# Mach_trai_tim.net
KiCad netlist of a schematic drawn in Altium Designer
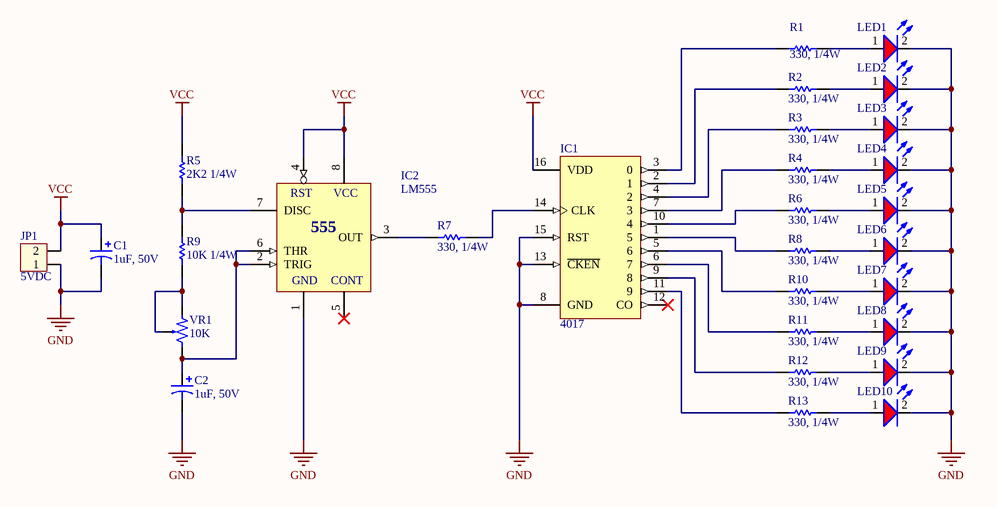
[diagram p0: Mach trai tim.SchDoc]

(export (version "E")
  (design (tool "Eeschema 10.0.6"))
  (components
    (comp (ref "C1")
      (value "1uF, 50V")
      (footprint "CAP_1UF_50V")
      (description "CAP GSR 0511 10uF 16V 20%")
      (fields (field (name "Comment") "GSR10M016-0511TAF"))
      (libsource (lib "lpson") (part "GSR10M016-0511TAF"))
    )
    (comp (ref "C2")
      (value "1uF, 50V")
      (footprint "CAP_1UF_50V")
      (description "CAP GSR 0511 10uF 16V 20%")
      (fields (field (name "Comment") "GSR10M016-0511TAF"))
      (libsource (lib "lpson") (part "GSR10M016-0511TAF"))
    )
    (comp (ref "IC1")
      (value "4017")
      (footprint "74HC4017")
      (description "Decade Counter/Divider with 10 Decoded Outputs")
      (fields (field (name "DESIGNED BY") "VanDungEvn"))
      (libsource (lib "lpson") (part "4017"))
    )
    (comp (ref "IC2")
      (value "LM555")
      (footprint "LM555")
      (description "Timer")
      (libsource (lib "lpson") (part "LM555"))
    )
    (comp (ref "JP1")
      (value "5VDC")
      (footprint "CON2")
      (description "Connector 2")
      (libsource (lib "lpson") (part "Con2"))
    )
    (comp (ref "LED1")
      (value "LED_R_5")
      (footprint "LED5R")
      (description "LED Red 5mm")
      (libsource (lib "lpson") (part "LED_RED_5MM"))
    )
    (comp (ref "LED2")
      (value "LED_R_5")
      (footprint "LED5R")
      (description "LED Red 5mm")
      (libsource (lib "lpson") (part "LED_RED_5MM"))
    )
    (comp (ref "LED3")
      (value "LED_R_5")
      (footprint "LED5R")
      (description "LED Red 5mm")
      (libsource (lib "lpson") (part "LED_RED_5MM"))
    )
    (comp (ref "LED4")
      (value "LED_R_5")
      (footprint "LED5R")
      (description "LED Red 5mm")
      (libsource (lib "lpson") (part "LED_RED_5MM"))
    )
    (comp (ref "LED5")
      (value "LED_R_5")
      (footprint "LED5R")
      (description "LED Red 5mm")
      (libsource (lib "lpson") (part "LED_RED_5MM"))
    )
    (comp (ref "LED6")
      (value "LED_R_5")
      (footprint "LED5R")
      (description "LED Red 5mm")
      (libsource (lib "lpson") (part "LED_RED_5MM"))
    )
    (comp (ref "LED7")
      (value "LED_R_5")
      (footprint "LED5R")
      (description "LED Red 5mm")
      (libsource (lib "lpson") (part "LED_RED_5MM"))
    )
    (comp (ref "LED8")
      (value "LED_R_5")
      (footprint "LED5R")
      (description "LED Red 5mm")
      (libsource (lib "lpson") (part "LED_RED_5MM"))
    )
    (comp (ref "LED9")
      (value "LED_R_5")
      (footprint "LED5R")
      (description "LED Red 5mm")
      (libsource (lib "lpson") (part "LED_RED_5MM"))
    )
    (comp (ref "LED10")
      (value "LED_R_5")
      (footprint "LED5R")
      (description "LED Red 5mm")
      (libsource (lib "lpson") (part "LED_RED_5MM"))
    )
    (comp (ref "R1")
      (value "330, 1/4W")
      (footprint "RES 1/4W CFR25")
      (description "RES CF AXIAL-0.3 5% 1/4W 1K")
      (fields (field (name "Comment") "CF1/4W1KJ25"))
      (libsource (lib "lpson") (part "CF1/4W1KJ25"))
    )
    (comp (ref "R2")
      (value "330, 1/4W")
      (footprint "RES 1/4W CFR25")
      (description "RES CF AXIAL-0.3 5% 1/4W 1K")
      (fields (field (name "Comment") "CF1/4W1KJ25"))
      (libsource (lib "lpson") (part "CF1/4W1KJ25"))
    )
    (comp (ref "R3")
      (value "330, 1/4W")
      (footprint "RES 1/4W CFR25")
      (description "RES CF AXIAL-0.3 5% 1/4W 1K")
      (fields (field (name "Comment") "CF1/4W1KJ25"))
      (libsource (lib "lpson") (part "CF1/4W1KJ25"))
    )
    (comp (ref "R4")
      (value "330, 1/4W")
      (footprint "RES 1/4W CFR25")
      (description "RES CF AXIAL-0.3 5% 1/4W 1K")
      (fields (field (name "Comment") "CF1/4W1KJ25"))
      (libsource (lib "lpson") (part "CF1/4W1KJ25"))
    )
    (comp (ref "R5")
      (value "2K2 1/4W")
      (footprint "RES 1/4W CFR25")
      (description "RES CF AXIAL-0.3 5% 1/4W 1K")
      (fields (field (name "Comment") "CF1/4W1KJ25"))
      (libsource (lib "lpson") (part "CF1/4W1KJ25"))
    )
    (comp (ref "R6")
      (value "330, 1/4W")
      (footprint "RES 1/4W CFR25")
      (description "RES CF AXIAL-0.3 5% 1/4W 1K")
      (fields (field (name "Comment") "CF1/4W1KJ25"))
      (libsource (lib "lpson") (part "CF1/4W1KJ25"))
    )
    (comp (ref "R7")
      (value "330, 1/4W")
      (footprint "RES 1/4W CFR25")
      (description "RES CF AXIAL-0.3 5% 1/4W 1K")
      (fields (field (name "Comment") "CF1/4W1KJ25"))
      (libsource (lib "lpson") (part "CF1/4W1KJ25"))
    )
    (comp (ref "R8")
      (value "330, 1/4W")
      (footprint "RES 1/4W CFR25")
      (description "RES CF AXIAL-0.3 5% 1/4W 1K")
      (fields (field (name "Comment") "CF1/4W1KJ25"))
      (libsource (lib "lpson") (part "CF1/4W1KJ25"))
    )
    (comp (ref "R9")
      (value "10K 1/4W")
      (footprint "RES 1/4W CFR25")
      (description "RES CF AXIAL-0.3 5% 1/4W 1K")
      (fields (field (name "Comment") "CF1/4W1KJ25"))
      (libsource (lib "lpson") (part "CF1/4W1KJ25"))
    )
    (comp (ref "R10")
      (value "330, 1/4W")
      (footprint "RES 1/4W CFR25")
      (description "RES CF AXIAL-0.3 5% 1/4W 1K")
      (fields (field (name "Comment") "CF1/4W1KJ25"))
      (libsource (lib "lpson") (part "CF1/4W1KJ25"))
    )
    (comp (ref "R11")
      (value "330, 1/4W")
      (footprint "RES 1/4W CFR25")
      (description "RES CF AXIAL-0.3 5% 1/4W 1K")
      (fields (field (name "Comment") "CF1/4W1KJ25"))
      (libsource (lib "lpson") (part "CF1/4W1KJ25"))
    )
    (comp (ref "R12")
      (value "330, 1/4W")
      (footprint "RES 1/4W CFR25")
      (description "RES CF AXIAL-0.3 5% 1/4W 1K")
      (fields (field (name "Comment") "CF1/4W1KJ25"))
      (libsource (lib "lpson") (part "CF1/4W1KJ25"))
    )
    (comp (ref "R13")
      (value "330, 1/4W")
      (footprint "RES 1/4W CFR25")
      (description "RES CF AXIAL-0.3 5% 1/4W 1K")
      (fields (field (name "Comment") "CF1/4W1KJ25"))
      (libsource (lib "lpson") (part "CF1/4W1KJ25"))
    )
    (comp (ref "VR1")
      (value "10K")
      (footprint "VR1")
      (description "Var Resistor")
      (libsource (lib "lpson") (part "VR2"))
    )
  )
  (nets
    (net (code "1") (name "GND") (class "Default")
      (node (ref "C1") (pin "2") (pinfunction "2_2") (pintype "passive"))
      (node (ref "C2") (pin "2") (pinfunction "2_2") (pintype "passive"))
      (node (ref "IC1") (pin "13") (pinfunction "~{CKEN}_13") (pintype "input"))
      (node (ref "IC1") (pin "15") (pinfunction "RST_15") (pintype "input"))
      (node (ref "IC1") (pin "8") (pinfunction "GND_8") (pintype "power_in"))
      (node (ref "IC2") (pin "1") (pinfunction "GND_1") (pintype "power_in"))
      (node (ref "JP1") (pin "1") (pinfunction "1_1") (pintype "passive"))
      (node (ref "LED1") (pin "2") (pinfunction "K_2") (pintype "passive"))
      (node (ref "LED10") (pin "2") (pinfunction "K_2") (pintype "passive"))
      (node (ref "LED2") (pin "2") (pinfunction "K_2") (pintype "passive"))
      (node (ref "LED3") (pin "2") (pinfunction "K_2") (pintype "passive"))
      (node (ref "LED4") (pin "2") (pinfunction "K_2") (pintype "passive"))
      (node (ref "LED5") (pin "2") (pinfunction "K_2") (pintype "passive"))
      (node (ref "LED6") (pin "2") (pinfunction "K_2") (pintype "passive"))
      (node (ref "LED7") (pin "2") (pinfunction "K_2") (pintype "passive"))
      (node (ref "LED8") (pin "2") (pinfunction "K_2") (pintype "passive"))
      (node (ref "LED9") (pin "2") (pinfunction "K_2") (pintype "passive"))
    )
    (net (code "2") (name "Net-(IC1-0)") (class "Default")
      (node (ref "IC1") (pin "3") (pinfunction "0_3") (pintype "output"))
      (node (ref "R1") (pin "1") (pinfunction "1_1") (pintype "passive"))
    )
    (net (code "3") (name "Net-(IC1-1)") (class "Default")
      (node (ref "IC1") (pin "2") (pinfunction "1_2") (pintype "output"))
      (node (ref "R2") (pin "1") (pinfunction "1_1") (pintype "passive"))
    )
    (net (code "4") (name "Net-(IC1-2)") (class "Default")
      (node (ref "IC1") (pin "4") (pinfunction "2_4") (pintype "output"))
      (node (ref "R3") (pin "1") (pinfunction "1_1") (pintype "passive"))
    )
    (net (code "5") (name "Net-(IC1-3)") (class "Default")
      (node (ref "IC1") (pin "7") (pinfunction "3_7") (pintype "output"))
      (node (ref "R4") (pin "1") (pinfunction "1_1") (pintype "passive"))
    )
    (net (code "6") (name "Net-(IC1-4)") (class "Default")
      (node (ref "IC1") (pin "10") (pinfunction "4_10") (pintype "output"))
      (node (ref "R6") (pin "1") (pinfunction "1_1") (pintype "passive"))
    )
    (net (code "7") (name "Net-(IC1-5)") (class "Default")
      (node (ref "IC1") (pin "1") (pinfunction "5_1") (pintype "output"))
      (node (ref "R8") (pin "1") (pinfunction "1_1") (pintype "passive"))
    )
    (net (code "8") (name "Net-(IC1-6)") (class "Default")
      (node (ref "IC1") (pin "5") (pinfunction "6_5") (pintype "output"))
      (node (ref "R10") (pin "1") (pinfunction "1_1") (pintype "passive"))
    )
    (net (code "9") (name "Net-(IC1-7)") (class "Default")
      (node (ref "IC1") (pin "6") (pinfunction "7_6") (pintype "output"))
      (node (ref "R11") (pin "1") (pinfunction "1_1") (pintype "passive"))
    )
    (net (code "10") (name "Net-(IC1-8)") (class "Default")
      (node (ref "IC1") (pin "9") (pinfunction "8_9") (pintype "output"))
      (node (ref "R12") (pin "1") (pinfunction "1_1") (pintype "passive"))
    )
    (net (code "11") (name "Net-(IC1-9)") (class "Default")
      (node (ref "IC1") (pin "11") (pinfunction "9_11") (pintype "output"))
      (node (ref "R13") (pin "1") (pinfunction "1_1") (pintype "passive"))
    )
    (net (code "12") (name "Net-(IC1-CLK)") (class "Default")
      (node (ref "IC1") (pin "14") (pinfunction "CLK_14") (pintype "input"))
      (node (ref "R7") (pin "2") (pinfunction "2_2") (pintype "passive"))
    )
    (net (code "13") (name "Net-(IC2-DISC)") (class "Default")
      (node (ref "IC2") (pin "7") (pinfunction "DISC_7") (pintype "open_collector"))
      (node (ref "R5") (pin "1") (pinfunction "1_1") (pintype "passive"))
      (node (ref "R9") (pin "2") (pinfunction "2_2") (pintype "passive"))
    )
    (net (code "14") (name "Net-(IC2-OUT)") (class "Default")
      (node (ref "IC2") (pin "3") (pinfunction "OUT_3") (pintype "output"))
      (node (ref "R7") (pin "1") (pinfunction "1_1") (pintype "passive"))
    )
    (net (code "15") (name "Net-(IC2-THR)") (class "Default")
      (node (ref "C2") (pin "1") (pinfunction "1_1") (pintype "passive"))
      (node (ref "IC2") (pin "2") (pinfunction "TRIG_2") (pintype "input"))
      (node (ref "IC2") (pin "6") (pinfunction "THR_6") (pintype "input"))
      (node (ref "VR1") (pin "3") (pinfunction "3_3") (pintype "passive"))
    )
    (net (code "16") (name "Net-(LED1-A)") (class "Default")
      (node (ref "LED1") (pin "1") (pinfunction "A_1") (pintype "passive"))
      (node (ref "R1") (pin "2") (pinfunction "2_2") (pintype "passive"))
    )
    (net (code "17") (name "Net-(LED2-A)") (class "Default")
      (node (ref "LED2") (pin "1") (pinfunction "A_1") (pintype "passive"))
      (node (ref "R2") (pin "2") (pinfunction "2_2") (pintype "passive"))
    )
    (net (code "18") (name "Net-(LED3-A)") (class "Default")
      (node (ref "LED3") (pin "1") (pinfunction "A_1") (pintype "passive"))
      (node (ref "R3") (pin "2") (pinfunction "2_2") (pintype "passive"))
    )
    (net (code "19") (name "Net-(LED4-A)") (class "Default")
      (node (ref "LED4") (pin "1") (pinfunction "A_1") (pintype "passive"))
      (node (ref "R4") (pin "2") (pinfunction "2_2") (pintype "passive"))
    )
    (net (code "20") (name "Net-(LED5-A)") (class "Default")
      (node (ref "LED5") (pin "1") (pinfunction "A_1") (pintype "passive"))
      (node (ref "R6") (pin "2") (pinfunction "2_2") (pintype "passive"))
    )
    (net (code "21") (name "Net-(LED6-A)") (class "Default")
      (node (ref "LED6") (pin "1") (pinfunction "A_1") (pintype "passive"))
      (node (ref "R8") (pin "2") (pinfunction "2_2") (pintype "passive"))
    )
    (net (code "22") (name "Net-(LED7-A)") (class "Default")
      (node (ref "LED7") (pin "1") (pinfunction "A_1") (pintype "passive"))
      (node (ref "R10") (pin "2") (pinfunction "2_2") (pintype "passive"))
    )
    (net (code "23") (name "Net-(LED8-A)") (class "Default")
      (node (ref "LED8") (pin "1") (pinfunction "A_1") (pintype "passive"))
      (node (ref "R11") (pin "2") (pinfunction "2_2") (pintype "passive"))
    )
    (net (code "24") (name "Net-(LED9-A)") (class "Default")
      (node (ref "LED9") (pin "1") (pinfunction "A_1") (pintype "passive"))
      (node (ref "R12") (pin "2") (pinfunction "2_2") (pintype "passive"))
    )
    (net (code "25") (name "Net-(LED10-A)") (class "Default")
      (node (ref "LED10") (pin "1") (pinfunction "A_1") (pintype "passive"))
      (node (ref "R13") (pin "2") (pinfunction "2_2") (pintype "passive"))
    )
    (net (code "26") (name "Net-(R9-Pad1)") (class "Default")
      (node (ref "R9") (pin "1") (pinfunction "1_1") (pintype "passive"))
      (node (ref "VR1") (pin "1") (pinfunction "1_1") (pintype "passive"))
      (node (ref "VR1") (pin "2") (pinfunction "2_2") (pintype "passive"))
    )
    (net (code "27") (name "VCC") (class "Default")
      (node (ref "C1") (pin "1") (pinfunction "1_1") (pintype "passive"))
      (node (ref "IC1") (pin "16") (pinfunction "VDD_16") (pintype "power_in"))
      (node (ref "IC2") (pin "4") (pinfunction "RST_4") (pintype "input"))
      (node (ref "IC2") (pin "8") (pinfunction "VCC_8") (pintype "power_in"))
      (node (ref "JP1") (pin "2") (pinfunction "2_2") (pintype "passive"))
      (node (ref "R5") (pin "2") (pinfunction "2_2") (pintype "passive"))
    )
    (net (code "28") (name "unconnected-(IC1-CO-Pad12)") (class "Default")
      (node (ref "IC1") (pin "12") (pinfunction "CO_12") (pintype "output+no_connect"))
    )
    (net (code "29") (name "unconnected-(IC2-CONT-Pad5)") (class "Default")
      (node (ref "IC2") (pin "5") (pinfunction "CONT_5") (pintype "passive+no_connect"))
    )
  )
)
